# 5V_to_3V3.net
KiCad netlist of a schematic drawn in Altium Designer
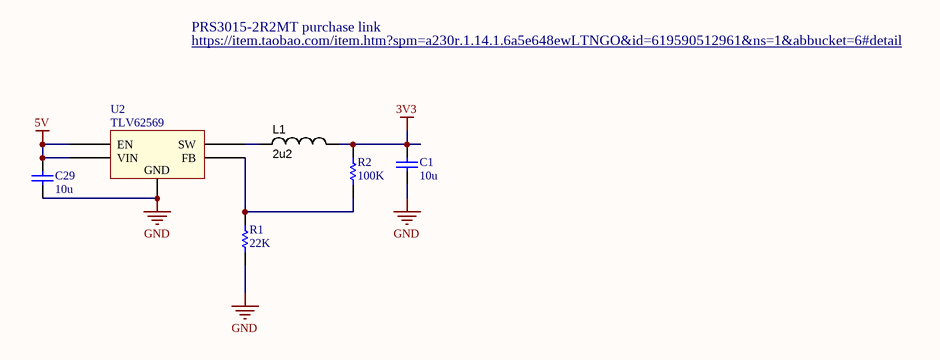
[diagram p0: 5V_to_3V3.SchDoc]

(export (version "E")
  (design (tool "Eeschema 10.0.6"))
  (components
    (comp (ref "C1")
      (value "10u")
      (footprint "CAPC2012X135N")
      (description "Capacitor")
      (fields (field (name "Comment") "Cap") (field (name "PUBLISHER") "Altium Limited"))
      (libsource (lib "IOBoard_Low") (part "Cap"))
    )
    (comp (ref "C29")
      (value "10u")
      (footprint "CAPC2012X135N")
      (description "Capacitor")
      (fields (field (name "Comment") "Cap") (field (name "PUBLISHER") "Altium Limited"))
      (libsource (lib "IOBoard_Low") (part "Cap"))
    )
    (comp (ref "L1")
      (value "2u2")
      (footprint "INDM3225X240N")
      (description "IHLP SMD 4040")
      (fields (field (name "Comment") "inductor"))
      (libsource (lib "IOBoard_Low") (part "INDC"))
    )
    (comp (ref "R1")
      (value "22K")
      (footprint "RESC2012X70N")
      (description "Resistor")
      (fields (field (name "Comment") "Res1") (field (name "PUBLISHER") "Altium Limited"))
      (libsource (lib "IOBoard_Low") (part "Res1"))
    )
    (comp (ref "R2")
      (value "100K")
      (footprint "RESC2012X70N")
      (description "Resistor")
      (fields (field (name "Comment") "Res1") (field (name "PUBLISHER") "Altium Limited"))
      (libsource (lib "IOBoard_Low") (part "Res1"))
    )
    (comp (ref "U2")
      (value "TLV62569")
      (footprint "SOT23-5")
      (description "2-A High Efficiency Synchronous Buck Converter in SOT Package")
      (fields (field (name "MANUFACTURER") "TI"))
      (libsource (lib "IOBoard") (part "TLV62569"))
    )
  )
  (nets
    (net (code "1") (name "3V3") (class "Default")
      (node (ref "C1") (pin "2") (pinfunction "2_2") (pintype "passive"))
      (node (ref "L1") (pin "2") (pinfunction "2_2") (pintype "passive"))
      (node (ref "R2") (pin "2") (pinfunction "2_2") (pintype "passive"))
    )
    (net (code "2") (name "5V") (class "Default")
      (node (ref "C29") (pin "2") (pinfunction "2_2") (pintype "passive"))
      (node (ref "U2") (pin "1") (pinfunction "EN_1") (pintype "passive"))
      (node (ref "U2") (pin "4") (pinfunction "VIN_4") (pintype "passive"))
    )
    (net (code "3") (name "GND") (class "Default")
      (node (ref "C1") (pin "1") (pinfunction "1_1") (pintype "passive"))
      (node (ref "C29") (pin "1") (pinfunction "1_1") (pintype "passive"))
      (node (ref "R1") (pin "2") (pinfunction "2_2") (pintype "passive"))
      (node (ref "U2") (pin "2") (pinfunction "GND_2") (pintype "passive"))
    )
    (net (code "4") (name "Net-(U2-FB)") (class "Default")
      (node (ref "R1") (pin "1") (pinfunction "1_1") (pintype "passive"))
      (node (ref "R2") (pin "1") (pinfunction "1_1") (pintype "passive"))
      (node (ref "U2") (pin "5") (pinfunction "FB_5") (pintype "passive"))
    )
    (net (code "5") (name "Net-(U2-SW)") (class "Default")
      (node (ref "L1") (pin "1") (pinfunction "1_1") (pintype "passive"))
      (node (ref "U2") (pin "3") (pinfunction "SW_3") (pintype "passive"))
    )
  )
)
